# GeekIMUv1.net
KiCad netlist of a schematic drawn in Altium Designer
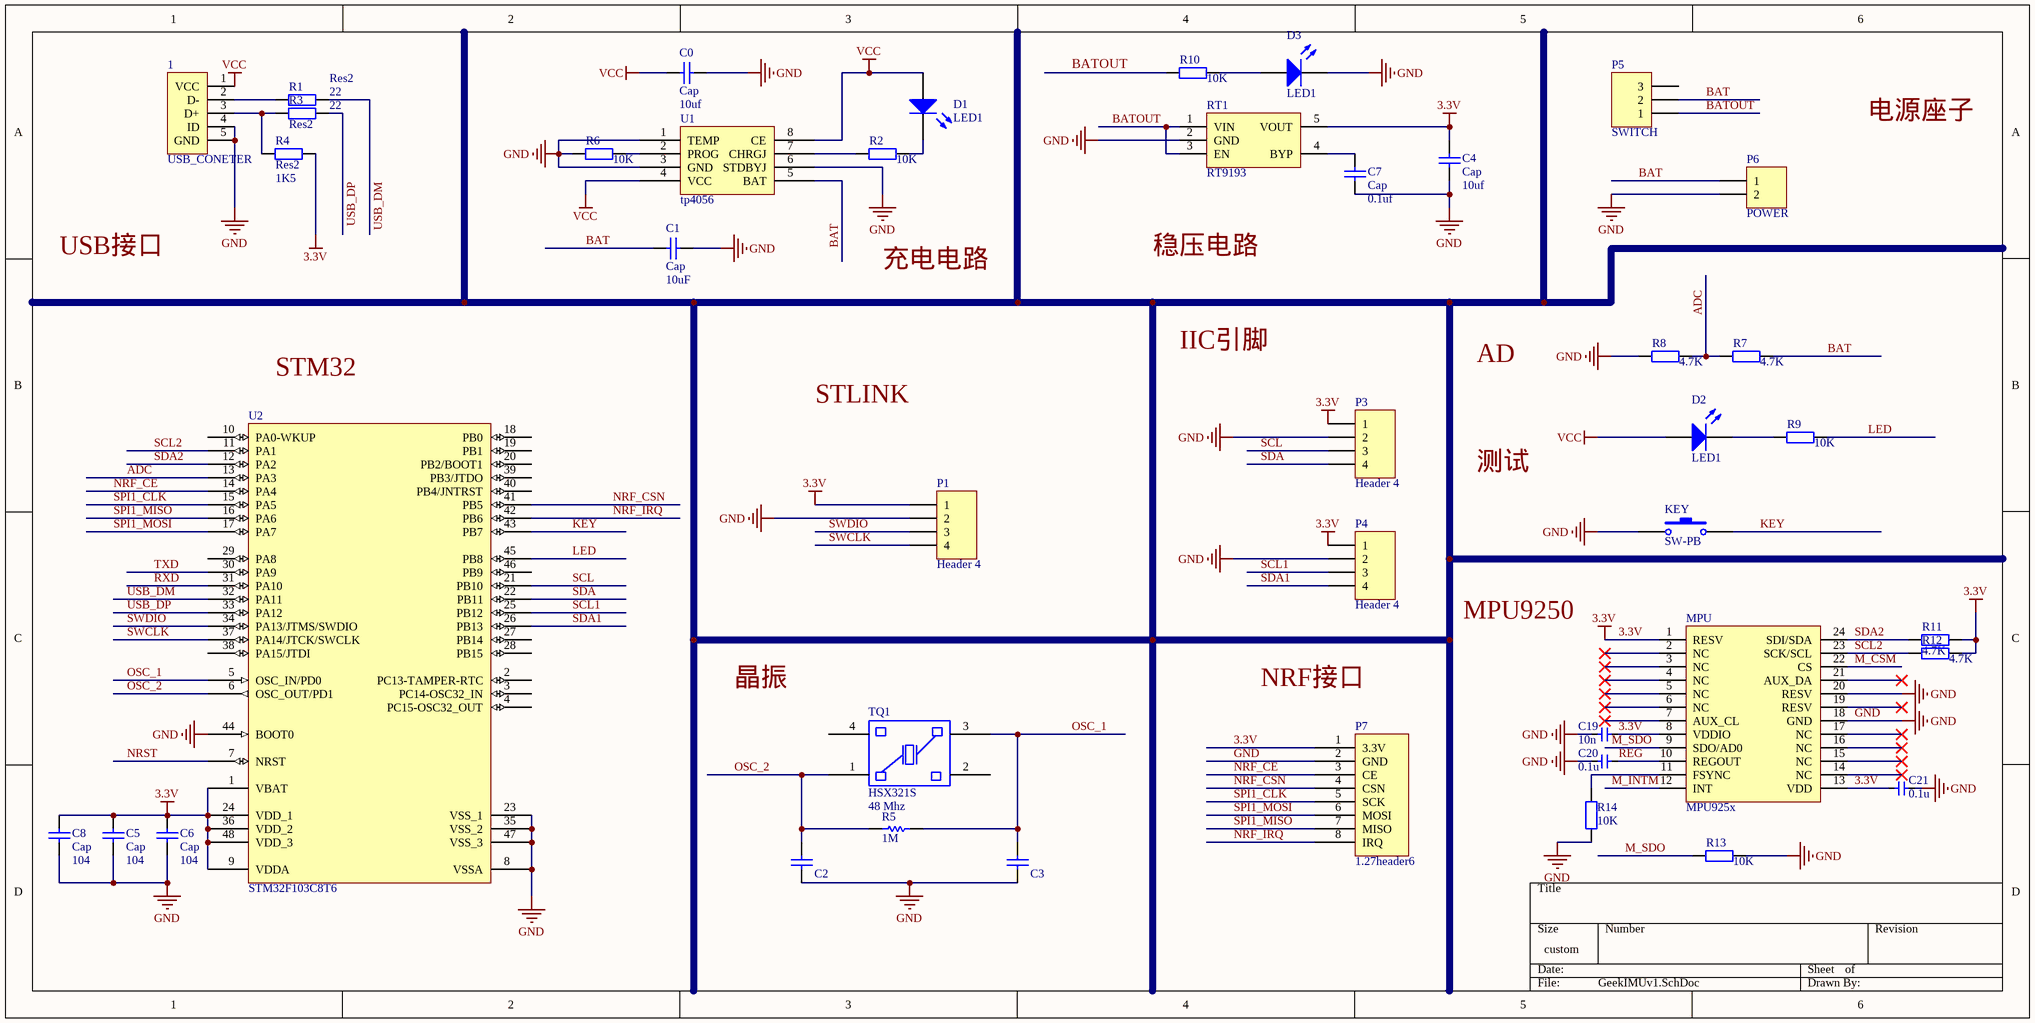
[diagram p0: GeekIMUv1.SchDoc]

(export (version "E")
  (design (tool "Eeschema 10.0.6"))
  (components
    (comp (ref "1")
      (value "USB_CONETER")
      (footprint "Mini USB")
      (description "USB")
      (fields (field (name "PUBLISHER") "Altium Limited"))
      (libsource (lib "my1012") (part "USB_conect_B"))
    )
    (comp (ref "C0")
      (value "Cap")
      (footprint "C0603")
      (description "Capacitor")
      (fields (field (name "ALTIUM_VALUE") "10uf") (field (name "PUBLISHER") "Altium Limited"))
      (libsource (lib "Miscellaneous Devices") (part "Cap"))
    )
    (comp (ref "C1")
      (value "Cap")
      (footprint "C0603")
      (description "Capacitor")
      (fields (field (name "ALTIUM_VALUE") "10uF") (field (name "PUBLISHER") "Altium Limited"))
      (libsource (lib "my1012") (part "Cap"))
    )
    (comp (ref "C2") (value "Cap") (footprint "C0402") (libsource (lib "refLib") (part "Cap")))
    (comp (ref "C3") (value "Cap") (footprint "C0402") (libsource (lib "refLib") (part "Cap")))
    (comp (ref "C4")
      (value "Cap")
      (footprint "C0603")
      (description "Capacitor")
      (fields (field (name "ALTIUM_VALUE") "10uf") (field (name "PUBLISHER") "Altium Limited"))
      (libsource (lib "Miscellaneous Devices") (part "Cap"))
    )
    (comp (ref "C5")
      (value "Cap")
      (footprint "C0402")
      (description "Capacitor")
      (fields (field (name "ALTIUM_VALUE") "104") (field (name "PUBLISHER") "Altium Limited"))
      (libsource (lib "my1012") (part "Cap"))
    )
    (comp (ref "C6")
      (value "Cap")
      (footprint "C0402")
      (description "Capacitor")
      (fields (field (name "ALTIUM_VALUE") "104") (field (name "PUBLISHER") "Altium Limited"))
      (libsource (lib "my1012") (part "Cap"))
    )
    (comp (ref "C7")
      (value "Cap")
      (footprint "B0402")
      (description "Capacitor")
      (fields (field (name "ALTIUM_VALUE") "0.1uf") (field (name "PUBLISHER") "Altium Limited"))
      (libsource (lib "Miscellaneous Devices") (part "Cap"))
    )
    (comp (ref "C8")
      (value "Cap")
      (footprint "C0402")
      (description "Capacitor")
      (fields (field (name "ALTIUM_VALUE") "104") (field (name "PUBLISHER") "Altium Limited"))
      (libsource (lib "my1012") (part "Cap"))
    )
    (comp (ref "C19")
      (value "10n")
      (footprint "C0402")
      (description "Capacitor")
      (fields (field (name "Comment") "Cap_0603"))
      (libsource (lib "SmartIMU") (part "Cap_0603"))
    )
    (comp (ref "C20")
      (value "0.1u")
      (footprint "C0402")
      (description "Capacitor")
      (fields (field (name "Comment") "Cap_0603"))
      (libsource (lib "SmartIMU") (part "Cap_0603"))
    )
    (comp (ref "C21")
      (value "0.1u")
      (footprint "C0402")
      (description "Capacitor")
      (fields (field (name "Comment") "Cap_0603"))
      (libsource (lib "SmartIMU") (part "Cap_0603"))
    )
    (comp (ref "D1")
      (value "LED1")
      (footprint "C0402")
      (description "Typical RED GaAs LED")
      (fields (field (name "PUBLISHER") "Altium Limited"))
      (libsource (lib "my1012") (part "LED1"))
    )
    (comp (ref "D2")
      (value "LED1")
      (footprint "C0402")
      (description "Typical RED GaAs LED")
      (fields (field (name "PUBLISHER") "Altium Limited"))
      (libsource (lib "my1012") (part "LED1"))
    )
    (comp (ref "D3")
      (value "LED1")
      (footprint "C0402")
      (description "Typical RED GaAs LED")
      (fields (field (name "PUBLISHER") "Altium Limited"))
      (libsource (lib "my1012") (part "LED1"))
    )
    (comp (ref "KEY")
      (value "SW-PB")
      (footprint "SW-SMD1")
      (description "Switch")
      (fields (field (name "PUBLISHER") "Altium Limited"))
      (libsource (lib "Miscellaneous Devices") (part "SW-PB"))
    )
    (comp (ref "MPU")
      (value "MPU925x")
      (footprint "QFN_P0.4_24")
      (description "Sensor Motion")
      (libsource (lib "SmartIMU") (part "MPU925x"))
    )
    (comp (ref "P1")
      (value "Header 4")
      (footprint "HDR1X4")
      (description "Header, 4-Pin")
      (fields (field (name "PUBLISHER") "Altium Limited"))
      (libsource (lib "Miscellaneous Connectors") (part "Header 4"))
    )
    (comp (ref "P3")
      (value "Header 4")
      (footprint "HDR1X4")
      (description "Header, 4-Pin")
      (fields (field (name "PUBLISHER") "Altium Limited"))
      (libsource (lib "Miscellaneous Connectors") (part "Header 4"))
    )
    (comp (ref "P4")
      (value "Header 4")
      (footprint "HDR1X4")
      (description "Header, 4-Pin")
      (fields (field (name "PUBLISHER") "Altium Limited"))
      (libsource (lib "Miscellaneous Connectors") (part "Header 4"))
    )
    (comp (ref "P5")
      (value "SWITCH")
      (footprint "HDR1X3")
      (description "Header, 3-Pin")
      (fields (field (name "PUBLISHER") "Altium Limited"))
      (libsource (lib "Miscellaneous Connectors") (part "Header 3"))
    )
    (comp (ref "P6")
      (value "POWER")
      (footprint "HDR1X2")
      (description "Header, 2-Pin")
      (fields (field (name "PUBLISHER") "Altium Limited"))
      (libsource (lib "Miscellaneous Connectors") (part "Header 2"))
    )
    (comp (ref "P7")
      (value "1.27header6")
      (footprint "1.27header6")
      (libsource (lib "1.27header6") (part "1.27header6"))
    )
    (comp (ref "R1")
      (value "Res2")
      (footprint "B0402")
      (description "Resistor")
      (fields (field (name "ALTIUM_VALUE") "22") (field (name "PUBLISHER") "Altium Limited"))
      (libsource (lib "") (part "Res2_2"))
    )
    (comp (ref "R2")
      (value "10K")
      (footprint "B0402")
      (description "Resistor")
      (fields (field (name "PUBLISHER") "Altium Limited"))
      (libsource (lib "") (part "Res2_1"))
    )
    (comp (ref "R3")
      (value "Res2")
      (footprint "B0402")
      (description "Resistor")
      (fields (field (name "ALTIUM_VALUE") "22") (field (name "PUBLISHER") "Altium Limited"))
      (libsource (lib "") (part "Res2_2"))
    )
    (comp (ref "R4")
      (value "Res2")
      (footprint "B0402")
      (description "Resistor")
      (fields (field (name "ALTIUM_VALUE") "1K5") (field (name "PUBLISHER") "Altium Limited"))
      (libsource (lib "") (part "Res2_2"))
    )
    (comp (ref "R5")
      (value "1M")
      (footprint "R0402")
      (description "Semiconductor Resistor")
      (fields (field (name "Comment") "Res Semi"))
      (libsource (lib "refLib") (part "Res Semi"))
    )
    (comp (ref "R6")
      (value "10K")
      (footprint "B0402")
      (description "Resistor")
      (fields (field (name "PUBLISHER") "Altium Limited"))
      (libsource (lib "") (part "Res2_1"))
    )
    (comp (ref "R7")
      (value "4.7K")
      (footprint "B0402")
      (description "Resistor")
      (fields (field (name "PUBLISHER") "Altium Limited"))
      (libsource (lib "") (part "Res2_1"))
    )
    (comp (ref "R8")
      (value "4.7K")
      (footprint "B0402")
      (description "Resistor")
      (fields (field (name "PUBLISHER") "Altium Limited"))
      (libsource (lib "") (part "Res2_1"))
    )
    (comp (ref "R9")
      (value "10K")
      (footprint "B0402")
      (description "Resistor")
      (fields (field (name "PUBLISHER") "Altium Limited"))
      (libsource (lib "") (part "Res2_1"))
    )
    (comp (ref "R10")
      (value "10K")
      (footprint "B0402")
      (description "Resistor")
      (fields (field (name "PUBLISHER") "Altium Limited"))
      (libsource (lib "") (part "Res2_1"))
    )
    (comp (ref "R11")
      (value "4.7K")
      (footprint "B0402")
      (description "Resistor")
      (fields (field (name "PUBLISHER") "Altium Limited"))
      (libsource (lib "") (part "Res2_1"))
    )
    (comp (ref "R12")
      (value "4.7K")
      (footprint "B0402")
      (description "Resistor")
      (fields (field (name "PUBLISHER") "Altium Limited"))
      (libsource (lib "") (part "Res2_1"))
    )
    (comp (ref "R13")
      (value "10K")
      (footprint "B0402")
      (description "Resistor")
      (fields (field (name "PUBLISHER") "Altium Limited"))
      (libsource (lib "") (part "Res2_1"))
    )
    (comp (ref "R14")
      (value "10K")
      (footprint "B0402")
      (description "Resistor")
      (fields (field (name "PUBLISHER") "Altium Limited"))
      (libsource (lib "my1012") (part "Res2"))
    )
    (comp (ref "RT1")
      (value "RT9193")
      (footprint "SOT23-5")
      (description "Power")
      (libsource (lib "SmartIMU") (part "RT9193"))
    )
    (comp (ref "TQ1")
      (value "HSX321S")
      (footprint "DSX321G")
      (description "XTAL")
      (fields (field (name "ALTIUM_VALUE") "48 Mhz"))
      (libsource (lib "refLib") (part "HSX321S"))
    )
    (comp (ref "U1") (value "tp4056") (footprint "SOP8") (libsource (lib "TP4056") (part "Component_1")))
    (comp (ref "U2")
      (value "STM32F103C8T6")
      (footprint "LQFP_P0.5_48")
      (description "STM32 ARM-based 32-bit MCU with 64 Kbytes Flash, 48-pin LQFP, Industrial Temperature")
      (fields (field (name "PUBLISHER") "Altium Limited"))
      (libsource (lib "ST Microcontroller 32-Bit STM32") (part "STM32F103C8T6"))
    )
  )
  (nets
    (net (code "2") (name "/ADC") (class "Default")
      (node (ref "R7") (pin "2") (pinfunction "2_2") (pintype "passive"))
      (node (ref "R8") (pin "1") (pinfunction "1_1") (pintype "passive"))
      (node (ref "U2") (pin "13") (pinfunction "PA3_13") (pintype "bidirectional"))
    )
    (net (code "3") (name "/BAT") (class "Default")
      (node (ref "C1") (pin "2") (pinfunction "2_2") (pintype "passive"))
      (node (ref "P5") (pin "2") (pinfunction "2_2") (pintype "passive"))
      (node (ref "P6") (pin "1") (pinfunction "1_1") (pintype "passive"))
      (node (ref "R7") (pin "1") (pinfunction "1_1") (pintype "passive"))
      (node (ref "U1") (pin "5") (pinfunction "BAT_5") (pintype "passive"))
    )
    (net (code "4") (name "/BATOUT") (class "Default")
      (node (ref "P5") (pin "1") (pinfunction "1_1") (pintype "passive"))
      (node (ref "R10") (pin "2") (pinfunction "2_2") (pintype "passive"))
      (node (ref "RT1") (pin "1") (pinfunction "VIN_1") (pintype "passive"))
      (node (ref "RT1") (pin "3") (pinfunction "EN_3") (pintype "power_in"))
    )
    (net (code "6") (name "/KEY") (class "Default")
      (node (ref "KEY") (pin "2") (pinfunction "2_2") (pintype "passive"))
      (node (ref "U2") (pin "43") (pinfunction "PB7_43") (pintype "bidirectional"))
    )
    (net (code "7") (name "/LED") (class "Default")
      (node (ref "R9") (pin "1") (pinfunction "1_1") (pintype "passive"))
      (node (ref "U2") (pin "45") (pinfunction "PB8_45") (pintype "bidirectional"))
    )
    (net (code "9") (name "/M_CSM") (class "Default")
      (node (ref "MPU") (pin "22") (pinfunction "CS_22") (pintype "passive"))
    )
    (net (code "10") (name "/M_INTM") (class "Default")
      (node (ref "MPU") (pin "12") (pinfunction "INT_12") (pintype "passive"))
    )
    (net (code "11") (name "/M_SDO") (class "Default")
      (node (ref "MPU") (pin "9") (pinfunction "SDO/AD0_9") (pintype "passive"))
      (node (ref "R13") (pin "2") (pinfunction "2_2") (pintype "passive"))
    )
    (net (code "12") (name "/NRF_CE") (class "Default")
      (node (ref "P7") (pin "3") (pinfunction "CE_3") (pintype "passive"))
      (node (ref "U2") (pin "14") (pinfunction "PA4_14") (pintype "bidirectional"))
    )
    (net (code "13") (name "/NRF_CSN") (class "Default")
      (node (ref "P7") (pin "4") (pinfunction "CSN_4") (pintype "passive"))
      (node (ref "U2") (pin "41") (pinfunction "PB5_41") (pintype "bidirectional"))
    )
    (net (code "14") (name "/NRF_IRQ") (class "Default")
      (node (ref "P7") (pin "8") (pinfunction "IRQ_8") (pintype "passive"))
      (node (ref "U2") (pin "42") (pinfunction "PB6_42") (pintype "bidirectional"))
    )
    (net (code "16") (name "/NRST") (class "Default")
      (node (ref "U2") (pin "7") (pinfunction "NRST_7") (pintype "bidirectional"))
    )
    (net (code "17") (name "/OSC_1") (class "Default")
      (node (ref "C3") (pin "2") (pinfunction "2_2") (pintype "passive"))
      (node (ref "R5") (pin "2") (pinfunction "2_2") (pintype "passive"))
      (node (ref "TQ1") (pin "3") (pinfunction "3_3") (pintype "passive"))
      (node (ref "U2") (pin "5") (pinfunction "OSC_IN/PD0_5") (pintype "input"))
    )
    (net (code "18") (name "/OSC_2") (class "Default")
      (node (ref "C2") (pin "2") (pinfunction "2_2") (pintype "passive"))
      (node (ref "R5") (pin "1") (pinfunction "1_1") (pintype "passive"))
      (node (ref "TQ1") (pin "1") (pinfunction "1_1") (pintype "passive"))
      (node (ref "U2") (pin "6") (pinfunction "OSC_OUT/PD1_6") (pintype "output"))
    )
    (net (code "19") (name "/REG") (class "Default")
      (node (ref "C20") (pin "2") (pinfunction "2_2") (pintype "passive"))
      (node (ref "MPU") (pin "10") (pinfunction "REGOUT_10") (pintype "passive"))
    )
    (net (code "20") (name "/RXD") (class "Default")
      (node (ref "U2") (pin "31") (pinfunction "PA10_31") (pintype "bidirectional"))
    )
    (net (code "21") (name "/SCL") (class "Default")
      (node (ref "P3") (pin "3") (pinfunction "3_3") (pintype "passive"))
      (node (ref "U2") (pin "21") (pinfunction "PB10_21") (pintype "bidirectional"))
    )
    (net (code "22") (name "/SCL1") (class "Default")
      (node (ref "P4") (pin "3") (pinfunction "3_3") (pintype "passive"))
      (node (ref "U2") (pin "25") (pinfunction "PB12_25") (pintype "bidirectional"))
    )
    (net (code "23") (name "/SCL2") (class "Default")
      (node (ref "MPU") (pin "23") (pinfunction "SCK/SCL_23") (pintype "passive"))
      (node (ref "R12") (pin "2") (pinfunction "2_2") (pintype "passive"))
      (node (ref "U2") (pin "11") (pinfunction "PA1_11") (pintype "bidirectional"))
    )
    (net (code "24") (name "/SDA") (class "Default")
      (node (ref "P3") (pin "4") (pinfunction "4_4") (pintype "passive"))
      (node (ref "U2") (pin "22") (pinfunction "PB11_22") (pintype "bidirectional"))
    )
    (net (code "25") (name "/SDA1") (class "Default")
      (node (ref "P4") (pin "4") (pinfunction "4_4") (pintype "passive"))
      (node (ref "U2") (pin "26") (pinfunction "PB13_26") (pintype "bidirectional"))
    )
    (net (code "26") (name "/SDA2") (class "Default")
      (node (ref "MPU") (pin "24") (pinfunction "SDI/SDA_24") (pintype "passive"))
      (node (ref "R11") (pin "2") (pinfunction "2_2") (pintype "passive"))
      (node (ref "U2") (pin "12") (pinfunction "PA2_12") (pintype "bidirectional"))
    )
    (net (code "27") (name "/SPI1_CLK") (class "Default")
      (node (ref "P7") (pin "5") (pinfunction "SCK_5") (pintype "passive"))
      (node (ref "U2") (pin "15") (pinfunction "PA5_15") (pintype "bidirectional"))
    )
    (net (code "28") (name "/SPI1_MISO") (class "Default")
      (node (ref "P7") (pin "7") (pinfunction "MISO_7") (pintype "passive"))
      (node (ref "U2") (pin "16") (pinfunction "PA6_16") (pintype "bidirectional"))
    )
    (net (code "29") (name "/SPI1_MOSI") (class "Default")
      (node (ref "P7") (pin "6") (pinfunction "MOSI_6") (pintype "passive"))
      (node (ref "U2") (pin "17") (pinfunction "PA7_17") (pintype "bidirectional"))
    )
    (net (code "32") (name "/SWCLK") (class "Default")
      (node (ref "P1") (pin "4") (pinfunction "4_4") (pintype "passive"))
      (node (ref "U2") (pin "37") (pinfunction "PA14/JTCK/SWCLK_37") (pintype "bidirectional"))
    )
    (net (code "33") (name "/SWDIO") (class "Default")
      (node (ref "P1") (pin "3") (pinfunction "3_3") (pintype "passive"))
      (node (ref "U2") (pin "34") (pinfunction "PA13/JTMS/SWDIO_34") (pintype "bidirectional"))
    )
    (net (code "34") (name "/TXD") (class "Default")
      (node (ref "U2") (pin "30") (pinfunction "PA9_30") (pintype "bidirectional"))
    )
    (net (code "35") (name "/USB_DM") (class "Default")
      (node (ref "R1") (pin "2") (pinfunction "2_2") (pintype "passive"))
      (node (ref "U2") (pin "32") (pinfunction "PA11_32") (pintype "bidirectional"))
    )
    (net (code "36") (name "/USB_DP") (class "Default")
      (node (ref "R3") (pin "2") (pinfunction "2_2") (pintype "passive"))
      (node (ref "U2") (pin "33") (pinfunction "PA12_33") (pintype "bidirectional"))
    )
    (net (code "43") (name "3.3V") (class "Default")
      (node (ref "C19") (pin "2") (pinfunction "2_2") (pintype "passive"))
      (node (ref "C21") (pin "2") (pinfunction "2_2") (pintype "passive"))
      (node (ref "C4") (pin "2") (pinfunction "2_2") (pintype "passive"))
      (node (ref "C5") (pin "2") (pinfunction "2_2") (pintype "passive"))
      (node (ref "C6") (pin "2") (pinfunction "2_2") (pintype "passive"))
      (node (ref "C8") (pin "2") (pinfunction "2_2") (pintype "passive"))
      (node (ref "MPU") (pin "1") (pinfunction "RESV_1") (pintype "passive"))
      (node (ref "MPU") (pin "13") (pinfunction "VDD_13") (pintype "passive"))
      (node (ref "MPU") (pin "8") (pinfunction "VDDIO_8") (pintype "passive"))
      (node (ref "P1") (pin "1") (pinfunction "1_1") (pintype "passive"))
      (node (ref "P3") (pin "1") (pinfunction "1_1") (pintype "passive"))
      (node (ref "P4") (pin "1") (pinfunction "1_1") (pintype "passive"))
      (node (ref "P7") (pin "1") (pinfunction "3.3V_1") (pintype "passive"))
      (node (ref "R11") (pin "1") (pinfunction "1_1") (pintype "passive"))
      (node (ref "R12") (pin "1") (pinfunction "1_1") (pintype "passive"))
      (node (ref "R4") (pin "2") (pinfunction "2_2") (pintype "passive"))
      (node (ref "RT1") (pin "5") (pinfunction "VOUT_5") (pintype "passive"))
      (node (ref "U2") (pin "1") (pinfunction "VBAT_1") (pintype "power_in"))
      (node (ref "U2") (pin "24") (pinfunction "VDD_1_24") (pintype "power_in"))
      (node (ref "U2") (pin "36") (pinfunction "VDD_2_36") (pintype "power_in"))
      (node (ref "U2") (pin "48") (pinfunction "VDD_3_48") (pintype "power_in"))
      (node (ref "U2") (pin "9") (pinfunction "VDDA_9") (pintype "power_in"))
    )
    (net (code "44") (name "GND") (class "Default")
      (node (ref "1") (pin "4") (pinfunction "ID_4") (pintype "passive"))
      (node (ref "1") (pin "5") (pinfunction "GND_5") (pintype "passive"))
      (node (ref "C0") (pin "2") (pinfunction "2_2") (pintype "passive"))
      (node (ref "C1") (pin "1") (pinfunction "1_1") (pintype "passive"))
      (node (ref "C19") (pin "1") (pinfunction "1_1") (pintype "passive"))
      (node (ref "C2") (pin "1") (pinfunction "1_1") (pintype "passive"))
      (node (ref "C20") (pin "1") (pinfunction "1_1") (pintype "passive"))
      (node (ref "C21") (pin "1") (pinfunction "1_1") (pintype "passive"))
      (node (ref "C3") (pin "1") (pinfunction "1_1") (pintype "passive"))
      (node (ref "C4") (pin "1") (pinfunction "1_1") (pintype "passive"))
      (node (ref "C5") (pin "1") (pinfunction "1_1") (pintype "passive"))
      (node (ref "C6") (pin "1") (pinfunction "1_1") (pintype "passive"))
      (node (ref "C7") (pin "1") (pinfunction "1_1") (pintype "passive"))
      (node (ref "C8") (pin "1") (pinfunction "1_1") (pintype "passive"))
      (node (ref "D3") (pin "2") (pinfunction "K_2") (pintype "passive"))
      (node (ref "KEY") (pin "1") (pinfunction "1_1") (pintype "passive"))
      (node (ref "MPU") (pin "18") (pinfunction "GND_18") (pintype "passive"))
      (node (ref "MPU") (pin "20") (pinfunction "RESV_20") (pintype "passive"))
      (node (ref "P1") (pin "2") (pinfunction "2_2") (pintype "passive"))
      (node (ref "P3") (pin "2") (pinfunction "2_2") (pintype "passive"))
      (node (ref "P4") (pin "2") (pinfunction "2_2") (pintype "passive"))
      (node (ref "P6") (pin "2") (pinfunction "2_2") (pintype "passive"))
      (node (ref "P7") (pin "2") (pinfunction "GND_2") (pintype "passive"))
      (node (ref "R13") (pin "1") (pinfunction "1_1") (pintype "passive"))
      (node (ref "R14") (pin "2") (pinfunction "2_2") (pintype "passive"))
      (node (ref "R6") (pin "2") (pinfunction "2_2") (pintype "passive"))
      (node (ref "R8") (pin "2") (pinfunction "2_2") (pintype "passive"))
      (node (ref "RT1") (pin "2") (pinfunction "GND_2") (pintype "passive"))
      (node (ref "U1") (pin "1") (pinfunction "TEMP_1") (pintype "passive"))
      (node (ref "U1") (pin "3") (pinfunction "GND_3") (pintype "passive"))
      (node (ref "U1") (pin "6") (pinfunction "STDBYJ_6") (pintype "passive"))
      (node (ref "U2") (pin "23") (pinfunction "VSS_1_23") (pintype "power_in"))
      (node (ref "U2") (pin "35") (pinfunction "VSS_2_35") (pintype "power_in"))
      (node (ref "U2") (pin "44") (pinfunction "BOOT0_44") (pintype "input"))
      (node (ref "U2") (pin "47") (pinfunction "VSS_3_47") (pintype "power_in"))
      (node (ref "U2") (pin "8") (pinfunction "VSSA_8") (pintype "power_in"))
    )
    (net (code "45") (name "Net-(1-D+)") (class "Default")
      (node (ref "1") (pin "3") (pinfunction "D+_3") (pintype "passive"))
      (node (ref "R3") (pin "1") (pinfunction "1_1") (pintype "passive"))
      (node (ref "R4") (pin "1") (pinfunction "1_1") (pintype "passive"))
    )
    (net (code "46") (name "Net-(1-D-)") (class "Default")
      (node (ref "1") (pin "2") (pinfunction "D-_2") (pintype "passive"))
      (node (ref "R1") (pin "1") (pinfunction "1_1") (pintype "passive"))
    )
    (net (code "47") (name "Net-(D1-K)") (class "Default")
      (node (ref "D1") (pin "2") (pinfunction "K_2") (pintype "passive"))
      (node (ref "R2") (pin "1") (pinfunction "1_1") (pintype "passive"))
    )
    (net (code "48") (name "Net-(D2-K)") (class "Default")
      (node (ref "D2") (pin "2") (pinfunction "K_2") (pintype "passive"))
      (node (ref "R9") (pin "2") (pinfunction "2_2") (pintype "passive"))
    )
    (net (code "49") (name "Net-(D3-A)") (class "Default")
      (node (ref "D3") (pin "1") (pinfunction "A_1") (pintype "passive"))
      (node (ref "R10") (pin "1") (pinfunction "1_1") (pintype "passive"))
    )
    (net (code "50") (name "Net-(MPU-FSYNC)") (class "Default")
      (node (ref "MPU") (pin "11") (pinfunction "FSYNC_11") (pintype "passive"))
      (node (ref "R14") (pin "1") (pinfunction "1_1") (pintype "passive"))
    )
    (net (code "51") (name "Net-(RT1-BYP)") (class "Default")
      (node (ref "C7") (pin "2") (pinfunction "2_2") (pintype "passive"))
      (node (ref "RT1") (pin "4") (pinfunction "BYP_4") (pintype "passive"))
    )
    (net (code "52") (name "Net-(U1-CHRGJ)") (class "Default")
      (node (ref "R2") (pin "2") (pinfunction "2_2") (pintype "passive"))
      (node (ref "U1") (pin "7") (pinfunction "CHRGJ_7") (pintype "passive"))
    )
    (net (code "53") (name "Net-(U1-PROG)") (class "Default")
      (node (ref "R6") (pin "1") (pinfunction "1_1") (pintype "passive"))
      (node (ref "U1") (pin "2") (pinfunction "PROG_2") (pintype "passive"))
    )
    (net (code "54") (name "VCC") (class "Default")
      (node (ref "1") (pin "1") (pinfunction "VCC_1") (pintype "passive"))
      (node (ref "C0") (pin "1") (pinfunction "1_1") (pintype "passive"))
      (node (ref "D1") (pin "1") (pinfunction "A_1") (pintype "passive"))
      (node (ref "D2") (pin "1") (pinfunction "A_1") (pintype "passive"))
      (node (ref "U1") (pin "4") (pinfunction "VCC_4") (pintype "passive"))
      (node (ref "U1") (pin "8") (pinfunction "CE_8") (pintype "passive"))
    )
    (net (code "55") (name "unconnected-(MPU-AUX_CL-Pad7)") (class "Default")
      (node (ref "MPU") (pin "7") (pinfunction "AUX_CL_7") (pintype "passive+no_connect"))
    )
    (net (code "56") (name "unconnected-(MPU-AUX_DA-Pad21)") (class "Default")
      (node (ref "MPU") (pin "21") (pinfunction "AUX_DA_21") (pintype "passive+no_connect"))
    )
    (net (code "57") (name "unconnected-(MPU-NC-Pad2)") (class "Default")
      (node (ref "MPU") (pin "2") (pinfunction "NC_2") (pintype "passive+no_connect"))
    )
    (net (code "58") (name "unconnected-(MPU-NC-Pad3)") (class "Default")
      (node (ref "MPU") (pin "3") (pinfunction "NC_3") (pintype "passive+no_connect"))
    )
    (net (code "59") (name "unconnected-(MPU-NC-Pad4)") (class "Default")
      (node (ref "MPU") (pin "4") (pinfunction "NC_4") (pintype "passive+no_connect"))
    )
    (net (code "60") (name "unconnected-(MPU-NC-Pad5)") (class "Default")
      (node (ref "MPU") (pin "5") (pinfunction "NC_5") (pintype "passive+no_connect"))
    )
    (net (code "61") (name "unconnected-(MPU-NC-Pad6)") (class "Default")
      (node (ref "MPU") (pin "6") (pinfunction "NC_6") (pintype "passive+no_connect"))
    )
    (net (code "62") (name "unconnected-(MPU-NC-Pad14)") (class "Default")
      (node (ref "MPU") (pin "14") (pinfunction "NC_14") (pintype "passive+no_connect"))
    )
    (net (code "63") (name "unconnected-(MPU-NC-Pad15)") (class "Default")
      (node (ref "MPU") (pin "15") (pinfunction "NC_15") (pintype "passive+no_connect"))
    )
    (net (code "64") (name "unconnected-(MPU-NC-Pad16)") (class "Default")
      (node (ref "MPU") (pin "16") (pinfunction "NC_16") (pintype "passive+no_connect"))
    )
    (net (code "65") (name "unconnected-(MPU-NC-Pad17)") (class "Default")
      (node (ref "MPU") (pin "17") (pinfunction "NC_17") (pintype "passive+no_connect"))
    )
    (net (code "66") (name "unconnected-(MPU-RESV-Pad19)") (class "Default")
      (node (ref "MPU") (pin "19") (pinfunction "RESV_19") (pintype "passive+no_connect"))
    )
    (net (code "67") (name "unconnected-(P5-Pad3)") (class "Default")
      (node (ref "P5") (pin "3") (pinfunction "3_3") (pintype "passive"))
    )
    (net (code "68") (name "unconnected-(TQ1-Pad2)") (class "Default")
      (node (ref "TQ1") (pin "2") (pinfunction "2_2") (pintype "passive"))
    )
    (net (code "69") (name "unconnected-(TQ1-Pad4)") (class "Default")
      (node (ref "TQ1") (pin "4") (pinfunction "4_4") (pintype "passive"))
    )
    (net (code "70") (name "unconnected-(U2-PA0-WKUP-Pad10)") (class "Default")
      (node (ref "U2") (pin "10") (pinfunction "PA0-WKUP_10") (pintype "bidirectional"))
    )
    (net (code "71") (name "unconnected-(U2-PA8-Pad29)") (class "Default")
      (node (ref "U2") (pin "29") (pinfunction "PA8_29") (pintype "bidirectional"))
    )
    (net (code "72") (name "unconnected-(U2-PA15{slash}JTDI-Pad38)") (class "Default")
      (node (ref "U2") (pin "38") (pinfunction "PA15/JTDI_38") (pintype "bidirectional"))
    )
    (net (code "73") (name "unconnected-(U2-PB0-Pad18)") (class "Default")
      (node (ref "U2") (pin "18") (pinfunction "PB0_18") (pintype "bidirectional"))
    )
    (net (code "74") (name "unconnected-(U2-PB1-Pad19)") (class "Default")
      (node (ref "U2") (pin "19") (pinfunction "PB1_19") (pintype "bidirectional"))
    )
    (net (code "75") (name "unconnected-(U2-PB2{slash}BOOT1-Pad20)") (class "Default")
      (node (ref "U2") (pin "20") (pinfunction "PB2/BOOT1_20") (pintype "bidirectional"))
    )
    (net (code "76") (name "unconnected-(U2-PB3{slash}JTDO-Pad39)") (class "Default")
      (node (ref "U2") (pin "39") (pinfunction "PB3/JTDO_39") (pintype "bidirectional"))
    )
    (net (code "77") (name "unconnected-(U2-PB4{slash}JNTRST-Pad40)") (class "Default")
      (node (ref "U2") (pin "40") (pinfunction "PB4/JNTRST_40") (pintype "bidirectional"))
    )
    (net (code "78") (name "unconnected-(U2-PB9-Pad46)") (class "Default")
      (node (ref "U2") (pin "46") (pinfunction "PB9_46") (pintype "bidirectional"))
    )
    (net (code "79") (name "unconnected-(U2-PB14-Pad27)") (class "Default")
      (node (ref "U2") (pin "27") (pinfunction "PB14_27") (pintype "bidirectional"))
    )
    (net (code "80") (name "unconnected-(U2-PB15-Pad28)") (class "Default")
      (node (ref "U2") (pin "28") (pinfunction "PB15_28") (pintype "bidirectional"))
    )
    (net (code "81") (name "unconnected-(U2-PC13-TAMPER-RTC-Pad2)") (class "Default")
      (node (ref "U2") (pin "2") (pinfunction "PC13-TAMPER-RTC_2") (pintype "bidirectional"))
    )
    (net (code "82") (name "unconnected-(U2-PC14-OSC32_IN-Pad3)") (class "Default")
      (node (ref "U2") (pin "3") (pinfunction "PC14-OSC32_IN_3") (pintype "bidirectional"))
    )
    (net (code "83") (name "unconnected-(U2-PC15-OSC32_OUT-Pad4)") (class "Default")
      (node (ref "U2") (pin "4") (pinfunction "PC15-OSC32_OUT_4") (pintype "bidirectional"))
    )
  )
)
